# MCU.net
KiCad netlist of a schematic drawn in Altium Designer
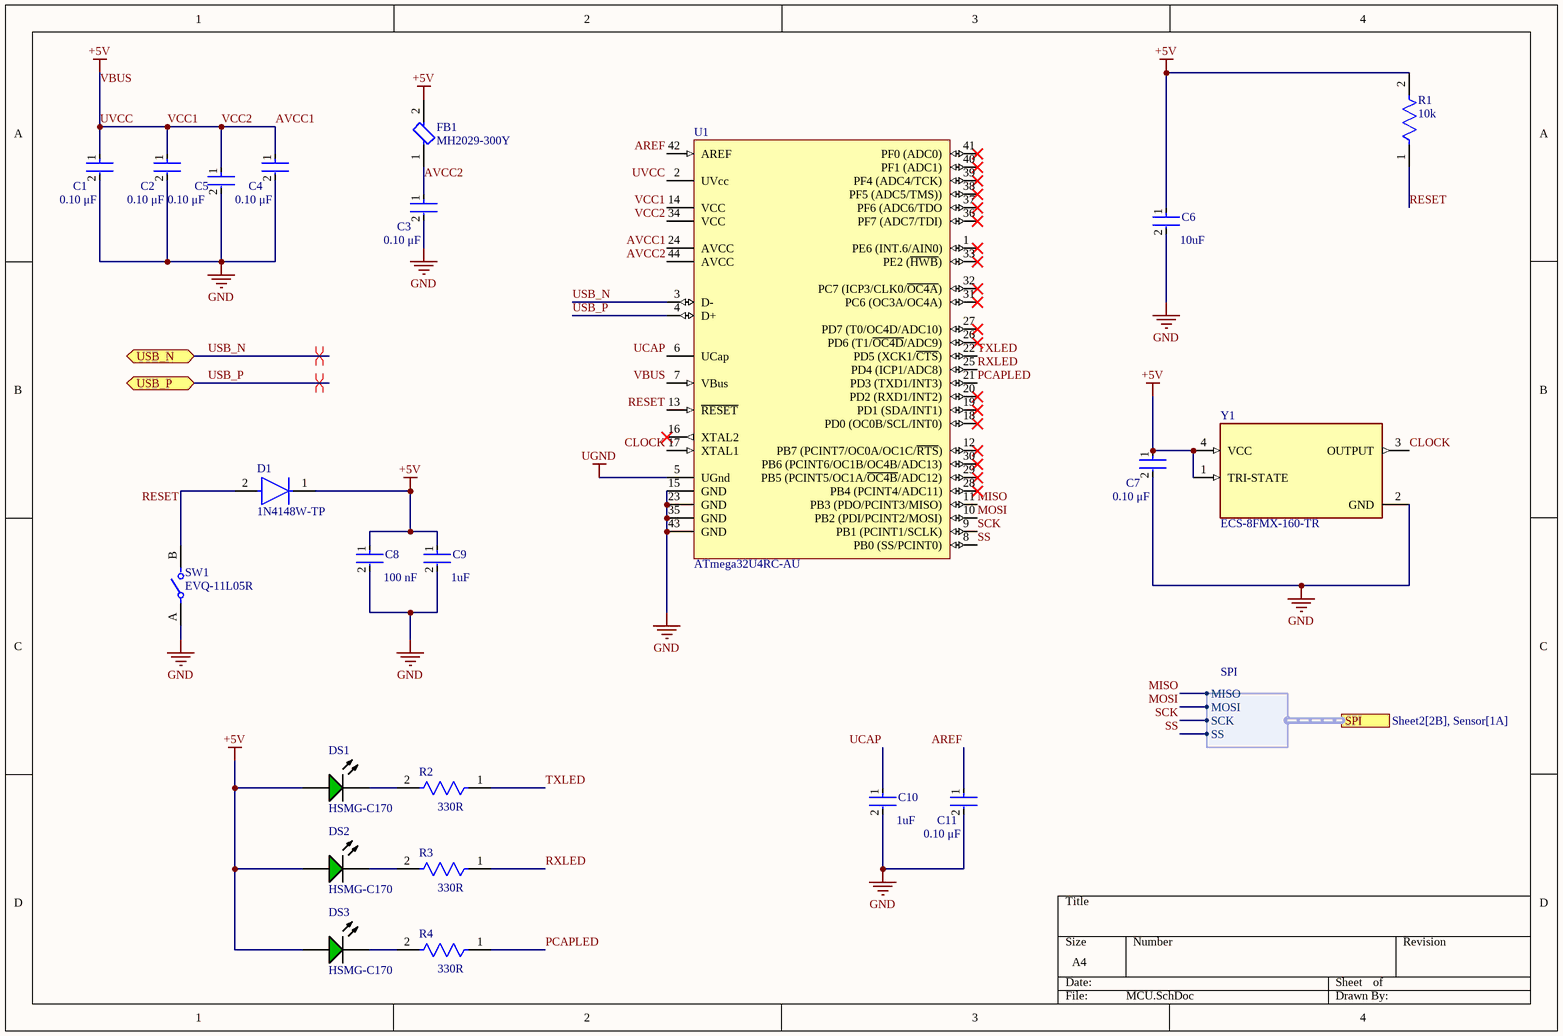
[diagram p0: MCU.SchDoc]

(export (version "E")
  (design (tool "Eeschema 10.0.6"))
  (components
    (comp (ref "C1")
      (value "C0805C104J8RACTU")
      (footprint "FP-C0805C-DN-MFG")
      (description "CAP CER 0.1UF 10V 5% X7R 0805")
      (fields
        (field (name "MANUFACTURER") "KEMET")
        (field (name "TOLERANCE") "0.05")
        (field (name "CAPACITANCE") "0.10 μF")
      )
      (libsource (lib "Altium Content Vault") (part "b4654b650e69147ec39a6b967a45e02"))
    )
    (comp (ref "C2")
      (value "C0805C104J8RACTU")
      (footprint "FP-C0805C-DN-MFG")
      (description "CAP CER 0.1UF 10V 5% X7R 0805")
      (fields
        (field (name "MANUFACTURER") "KEMET")
        (field (name "TOLERANCE") "0.05")
        (field (name "CAPACITANCE") "0.10 μF")
      )
      (libsource (lib "Altium Content Vault") (part "b4654b650e69147ec39a6b967a45e02"))
    )
    (comp (ref "C3")
      (value "C0805C104J8RACTU")
      (footprint "FP-C0805C-DN-MFG")
      (description "CAP CER 0.1UF 10V 5% X7R 0805")
      (fields
        (field (name "MANUFACTURER") "KEMET")
        (field (name "TOLERANCE") "0.05")
        (field (name "CAPACITANCE") "0.10 μF")
      )
      (libsource (lib "Altium Content Vault") (part "b4654b650e69147ec39a6b967a45e02"))
    )
    (comp (ref "C4")
      (value "C0805C104J8RACTU")
      (footprint "FP-C0805C-DN-MFG")
      (description "CAP CER 0.1UF 10V 5% X7R 0805")
      (fields
        (field (name "MANUFACTURER") "KEMET")
        (field (name "TOLERANCE") "0.05")
        (field (name "CAPACITANCE") "0.10 μF")
      )
      (libsource (lib "Altium Content Vault") (part "b4654b650e69147ec39a6b967a45e02"))
    )
    (comp (ref "C5")
      (value "C0805C104J8RACTU")
      (footprint "FP-C0805C-DN-MFG")
      (description "CAP CER 0.1UF 10V 5% X7R 0805")
      (fields
        (field (name "MANUFACTURER") "KEMET")
        (field (name "TOLERANCE") "0.05")
        (field (name "CAPACITANCE") "0.10 μF")
      )
      (libsource (lib "Altium Content Vault") (part "b4654b650e69147ec39a6b967a45e02"))
    )
    (comp (ref "C6")
      (value "C0805C106K8PACTU")
      (footprint "FP-C0805C-DG-MFG")
      (description "CAP CER 10UF 10V X5R 0805")
      (fields
        (field (name "TOLERANCE") "10%")
        (field (name "MANUFACTURER") "Kemet")
        (field (name "CAPACITANCE") "10uF")
      )
      (libsource (lib "Altium Content Vault") (part "11868f565c42a9108669ba33697ecf6"))
    )
    (comp (ref "C7")
      (value "C0805C104J8RACTU")
      (footprint "FP-C0805C-DN-MFG")
      (description "CAP CER 0.1UF 10V 5% X7R 0805")
      (fields
        (field (name "MANUFACTURER") "KEMET")
        (field (name "TOLERANCE") "0.05")
        (field (name "CAPACITANCE") "0.10 μF")
      )
      (libsource (lib "Altium Content Vault") (part "b4654b650e69147ec39a6b967a45e02"))
    )
    (comp (ref "C8")
      (value "CC0805KRX7R7BB104")
      (footprint "FP-CC0805-0_85-MFG")
      (description "CAP CER 0.1UF 16V X7R 0805")
      (fields
        (field (name "MANUFACTURER") "Yageo")
        (field (name "OCTOPART") "https://octopart.com/cc0805krx7r7bb104-yageo-39467769")
        (field (name "CAPACITANCE") "100 nF")
      )
      (libsource (lib "Altium Content Vault") (part "11868f565c42a9108669ba33697ecf6"))
    )
    (comp (ref "C9")
      (value "C0805C106K8PACTU")
      (footprint "FP-C0805C-DG-MFG")
      (description "CAP CER 10UF 10V X5R 0805")
      (fields
        (field (name "TOLERANCE") "10%")
        (field (name "MANUFACTURER") "Kemet")
        (field (name "CAPACITANCE") "1uF")
      )
      (libsource (lib "Altium Content Vault") (part "11868f565c42a9108669ba33697ecf6"))
    )
    (comp (ref "C10")
      (value "C0805C106K8PACTU")
      (footprint "FP-C0805C-DG-MFG")
      (description "CAP CER 10UF 10V X5R 0805")
      (fields
        (field (name "TOLERANCE") "10%")
        (field (name "MANUFACTURER") "Kemet")
        (field (name "CAPACITANCE") "1uF")
      )
      (libsource (lib "Altium Content Vault") (part "11868f565c42a9108669ba33697ecf6"))
    )
    (comp (ref "C11")
      (value "C0805C104J8RACTU")
      (footprint "FP-C0805C-DN-MFG")
      (description "CAP CER 0.1UF 10V 5% X7R 0805")
      (fields
        (field (name "MANUFACTURER") "KEMET")
        (field (name "TOLERANCE") "0.05")
        (field (name "CAPACITANCE") "0.10 μF")
      )
      (libsource (lib "Altium Content Vault") (part "b4654b650e69147ec39a6b967a45e02"))
    )
    (comp (ref "D1")
      (value "1N4148W-TP")
      (footprint "FP-SOD-123-IPC_A")
      (description "DIODE GEN PURP 100V 150MA SOD123")
      (libsource (lib "Altium Content Vault") (part "d7152d700b627762746794eb795d46e"))
    )
    (comp (ref "DS1")
      (value "HSMG-C170")
      (footprint "AVAG-HSMX-C170_V")
      (description "Chip LED, Green, 2.2 V, -40 to 85 degC, 2-Pin SMD, Pb-Free, Tape and Reel")
      (fields (field (name "MANUFACTURER") "Avago"))
      (libsource (lib "Altium Content Vault") (part "LED_GREEN_A1K2-2"))
    )
    (comp (ref "DS2")
      (value "HSMG-C170")
      (footprint "AVAG-HSMX-C170_V")
      (description "Chip LED, Green, 2.2 V, -40 to 85 degC, 2-Pin SMD, Pb-Free, Tape and Reel")
      (fields (field (name "MANUFACTURER") "Avago"))
      (libsource (lib "Altium Content Vault") (part "LED_GREEN_A1K2-2"))
    )
    (comp (ref "DS3")
      (value "HSMG-C170")
      (footprint "AVAG-HSMX-C170_V")
      (description "Chip LED, Green, 2.2 V, -40 to 85 degC, 2-Pin SMD, Pb-Free, Tape and Reel")
      (fields (field (name "MANUFACTURER") "Avago"))
      (libsource (lib "Altium Content Vault") (part "LED_GREEN_A1K2-2"))
    )
    (comp (ref "FB1")
      (value "MH2029-300Y")
      (footprint "FP-MH2029-MFG")
      (description "MH Series High Current Chip Ferrite Beads")
      (fields (field (name "OCTOPART") "https://octopart.com/mh2029-300y-bourns-756929"))
      (libsource (lib "Altium Content Vault") (part "5f30dd21d616792df468990f7003faa"))
    )
    (comp (ref "R1")
      (value "CRCW080522R0FKEA")
      (footprint "FP-CRCW0805-e3-IPC_C")
      (description "RES Thick Film, 22Ω, 1%, 0.125W, 100ppm/°C, 0805")
      (fields (field (name "RESISTANCE") "10k") (field (name "TOLERANCE") "1%"))
      (libsource (lib "Altium Content Vault") (part "1029c3af85768c4190bb7ad29bc67b5"))
    )
    (comp (ref "R2")
      (value "330 R")
      (footprint "FP-CR0805-IPC_B")
      (description "Thick Film Chip Resistors 0805 330Ω 0.125W 1% 100ppm/°C")
      (fields (field (name "TOLERANCE") "1%") (field (name "RESISTANCE") "330R"))
      (libsource (lib "Altium Content Vault") (part "1029c3af85768c4190bb7ad29bc67b5"))
    )
    (comp (ref "R3")
      (value "330 R")
      (footprint "FP-CR0805-IPC_B")
      (description "Thick Film Chip Resistors 0805 330Ω 0.125W 1% 100ppm/°C")
      (fields (field (name "TOLERANCE") "1%") (field (name "RESISTANCE") "330R"))
      (libsource (lib "Altium Content Vault") (part "1029c3af85768c4190bb7ad29bc67b5"))
    )
    (comp (ref "R4")
      (value "330 R")
      (footprint "FP-CR0805-IPC_B")
      (description "Thick Film Chip Resistors 0805 330Ω 0.125W 1% 100ppm/°C")
      (fields (field (name "TOLERANCE") "1%") (field (name "RESISTANCE") "330R"))
      (libsource (lib "Altium Content Vault") (part "1029c3af85768c4190bb7ad29bc67b5"))
    )
    (comp (ref "SW1")
      (value "EVQ-11L05R")
      (footprint "FP-EVQ-11L05R-MFG")
      (description "EVQ-11L05R Switch Tactile N.O. SPST Round Button PC Pins 0.02A 15VDC 1.6N Thru-Hole Radial T/R")
      (libsource (lib "Altium Content Vault") (part "2b0b2b19372efd94fa7681498149756"))
    )
    (comp (ref "U1")
      (value "ATmega32U4RC-AU")
      (footprint "44ML_N")
      (libsource (lib "Altium Content Vault") (part "MC-8B-ATM16U4-SQ44"))
    )
    (comp (ref "Y1")
      (value "ECS-8FMX-160-TR")
      (footprint "OSC_ECS-8FMX-160-TR")
      (description "CMOS Oscillator Enable/Disable 4-SOJ, 5.08mm pitch")
      (libsource (lib "University of Moratuwa") (part "ECS-8FMX-160-TR"))
    )
  )
  (nets
    (net (code "2") (name "+5V") (class "Default")
      (node (ref "C1") (pin "1") (pinfunction "1_1") (pintype "passive"))
      (node (ref "C2") (pin "1") (pinfunction "1_1") (pintype "passive"))
      (node (ref "C4") (pin "1") (pinfunction "1_1") (pintype "passive"))
      (node (ref "C5") (pin "1") (pinfunction "1_1") (pintype "passive"))
      (node (ref "C6") (pin "1") (pinfunction "1_1") (pintype "passive"))
      (node (ref "C7") (pin "1") (pinfunction "1_1") (pintype "passive"))
      (node (ref "C8") (pin "1") (pinfunction "1_1") (pintype "passive"))
      (node (ref "C9") (pin "1") (pinfunction "1_1") (pintype "passive"))
      (node (ref "D1") (pin "1") (pinfunction "C_1") (pintype "passive"))
      (node (ref "DS1") (pin "1") (pinfunction "A_1") (pintype "passive"))
      (node (ref "DS2") (pin "1") (pinfunction "A_1") (pintype "passive"))
      (node (ref "DS3") (pin "1") (pinfunction "A_1") (pintype "passive"))
      (node (ref "FB1") (pin "2") (pinfunction "2_2") (pintype "passive"))
      (node (ref "R1") (pin "2") (pinfunction "2_2") (pintype "passive"))
      (node (ref "U1") (pin "14") (pinfunction "VCC_14") (pintype "power_in"))
      (node (ref "U1") (pin "2") (pinfunction "UVcc_2") (pintype "power_in"))
      (node (ref "U1") (pin "24") (pinfunction "AVCC_24") (pintype "power_in"))
      (node (ref "U1") (pin "34") (pinfunction "VCC_34") (pintype "power_in"))
      (node (ref "U1") (pin "7") (pinfunction "VBus_7") (pintype "input"))
      (node (ref "Y1") (pin "1") (pinfunction "TRI-STATE_1") (pintype "input"))
      (node (ref "Y1") (pin "4") (pinfunction "VCC_4") (pintype "input"))
    )
    (net (code "3") (name "/AREF") (class "Default")
      (node (ref "C11") (pin "1") (pinfunction "1_1") (pintype "passive"))
      (node (ref "U1") (pin "42") (pinfunction "AREF_42") (pintype "input"))
    )
    (net (code "4") (name "/AVCC2") (class "Default")
      (node (ref "C3") (pin "1") (pinfunction "1_1") (pintype "passive"))
      (node (ref "FB1") (pin "1") (pinfunction "1_1") (pintype "passive"))
      (node (ref "U1") (pin "44") (pinfunction "AVCC_44") (pintype "power_in"))
    )
    (net (code "5") (name "/CLOCK") (class "Default")
      (node (ref "U1") (pin "17") (pinfunction "XTAL1_17") (pintype "input"))
      (node (ref "Y1") (pin "3") (pinfunction "OUTPUT_3") (pintype "output"))
    )
    (net (code "6") (name "/MISO") (class "Default")
      (node (ref "U1") (pin "11") (pinfunction "PB3_(PDO/PCINT3/MISO)_11") (pintype "bidirectional"))
    )
    (net (code "7") (name "/MOSI") (class "Default")
      (node (ref "U1") (pin "10") (pinfunction "PB2_(PDI/PCINT2/MOSI)_10") (pintype "bidirectional"))
    )
    (net (code "8") (name "/PCAPLED") (class "Default")
      (node (ref "R4") (pin "1") (pinfunction "1_1") (pintype "passive"))
      (node (ref "U1") (pin "21") (pinfunction "PD3_(TXD1/INT3)_21") (pintype "bidirectional"))
    )
    (net (code "9") (name "/RESET") (class "Default")
      (node (ref "D1") (pin "2") (pinfunction "A_2") (pintype "passive"))
      (node (ref "R1") (pin "1") (pinfunction "1_1") (pintype "passive"))
      (node (ref "SW1") (pin "B") (pinfunction "B_B") (pintype "passive"))
      (node (ref "U1") (pin "13") (pinfunction "~{RESET}_13") (pintype "input"))
    )
    (net (code "10") (name "/RXLED") (class "Default")
      (node (ref "R3") (pin "1") (pinfunction "1_1") (pintype "passive"))
      (node (ref "U1") (pin "25") (pinfunction "PD4_(ICP1/ADC8)_25") (pintype "bidirectional"))
    )
    (net (code "11") (name "/SCK") (class "Default")
      (node (ref "U1") (pin "9") (pinfunction "PB1_(PCINT1/SCLK)_9") (pintype "bidirectional"))
    )
    (net (code "12") (name "/SS") (class "Default")
      (node (ref "U1") (pin "8") (pinfunction "PB0_(SS/PCINT0)_8") (pintype "bidirectional"))
    )
    (net (code "13") (name "/TXLED") (class "Default")
      (node (ref "R2") (pin "1") (pinfunction "1_1") (pintype "passive"))
      (node (ref "U1") (pin "22") (pinfunction "PD5_(XCK1/~{CTS})_22") (pintype "bidirectional"))
    )
    (net (code "14") (name "/UCAP") (class "Default")
      (node (ref "C10") (pin "1") (pinfunction "1_1") (pintype "passive"))
      (node (ref "U1") (pin "6") (pinfunction "UCap_6") (pintype "passive"))
    )
    (net (code "15") (name "/USB_N") (class "Default")
      (node (ref "U1") (pin "3") (pinfunction "D-_3") (pintype "bidirectional"))
    )
    (net (code "16") (name "/USB_P") (class "Default")
      (node (ref "U1") (pin "4") (pinfunction "D+_4") (pintype "bidirectional"))
    )
    (net (code "18") (name "GND") (class "Default")
      (node (ref "C1") (pin "2") (pinfunction "2_2") (pintype "passive"))
      (node (ref "C10") (pin "2") (pinfunction "2_2") (pintype "passive"))
      (node (ref "C11") (pin "2") (pinfunction "2_2") (pintype "passive"))
      (node (ref "C2") (pin "2") (pinfunction "2_2") (pintype "passive"))
      (node (ref "C3") (pin "2") (pinfunction "2_2") (pintype "passive"))
      (node (ref "C4") (pin "2") (pinfunction "2_2") (pintype "passive"))
      (node (ref "C5") (pin "2") (pinfunction "2_2") (pintype "passive"))
      (node (ref "C6") (pin "2") (pinfunction "2_2") (pintype "passive"))
      (node (ref "C7") (pin "2") (pinfunction "2_2") (pintype "passive"))
      (node (ref "C8") (pin "2") (pinfunction "2_2") (pintype "passive"))
      (node (ref "C9") (pin "2") (pinfunction "2_2") (pintype "passive"))
      (node (ref "SW1") (pin "A") (pinfunction "A_A") (pintype "passive"))
      (node (ref "U1") (pin "15") (pinfunction "GND_15") (pintype "power_in"))
      (node (ref "U1") (pin "23") (pinfunction "GND_23") (pintype "power_in"))
      (node (ref "U1") (pin "35") (pinfunction "GND_35") (pintype "power_in"))
      (node (ref "U1") (pin "43") (pinfunction "GND_43") (pintype "power_in"))
      (node (ref "Y1") (pin "2") (pinfunction "GND_2") (pintype "power_in"))
    )
    (net (code "19") (name "Net-(DS1-K)") (class "Default")
      (node (ref "DS1") (pin "2") (pinfunction "K_2") (pintype "passive"))
      (node (ref "R2") (pin "2") (pinfunction "2_2") (pintype "passive"))
    )
    (net (code "20") (name "Net-(DS2-K)") (class "Default")
      (node (ref "DS2") (pin "2") (pinfunction "K_2") (pintype "passive"))
      (node (ref "R3") (pin "2") (pinfunction "2_2") (pintype "passive"))
    )
    (net (code "21") (name "Net-(DS3-K)") (class "Default")
      (node (ref "DS3") (pin "2") (pinfunction "K_2") (pintype "passive"))
      (node (ref "R4") (pin "2") (pinfunction "2_2") (pintype "passive"))
    )
    (net (code "22") (name "UGND") (class "Default")
      (node (ref "U1") (pin "5") (pinfunction "UGnd_5") (pintype "power_in"))
    )
    (net (code "23") (name "unconnected-(U1-PB4_(PCINT4{slash}ADC11)-Pad28)") (class "Default")
      (node (ref "U1") (pin "28") (pinfunction "PB4_(PCINT4/ADC11)_28") (pintype "bidirectional+no_connect"))
    )
    (net (code "24") (name "unconnected-(U1-PB5_(PCINT5{slash}OC1A{slash}~{OC4B}{slash}ADC12)-Pad29)") (class "Default")
      (node (ref "U1") (pin "29") (pinfunction "PB5_(PCINT5/OC1A/~{OC4B}/ADC12)_29") (pintype "bidirectional+no_connect"))
    )
    (net (code "25") (name "unconnected-(U1-PB6_(PCINT6{slash}OC1B{slash}OC4B{slash}ADC13)-Pad30)") (class "Default")
      (node (ref "U1") (pin "30") (pinfunction "PB6_(PCINT6/OC1B/OC4B/ADC13)_30") (pintype "bidirectional+no_connect"))
    )
    (net (code "26") (name "unconnected-(U1-PB7_(PCINT7{slash}OC0A{slash}OC1C{slash}~{RTS})-Pad12)") (class "Default")
      (node (ref "U1") (pin "12") (pinfunction "PB7_(PCINT7/OC0A/OC1C/~{RTS})_12") (pintype "bidirectional+no_connect"))
    )
    (net (code "27") (name "unconnected-(U1-PC6_(OC3A{slash}OC4A)-Pad31)") (class "Default")
      (node (ref "U1") (pin "31") (pinfunction "PC6_(OC3A/OC4A)_31") (pintype "bidirectional+no_connect"))
    )
    (net (code "28") (name "unconnected-(U1-PC7_(ICP3{slash}CLK0{slash}~{OC4A})-Pad32)") (class "Default")
      (node (ref "U1") (pin "32") (pinfunction "PC7_(ICP3/CLK0/~{OC4A})_32") (pintype "bidirectional+no_connect"))
    )
    (net (code "29") (name "unconnected-(U1-PD0_(OC0B{slash}SCL{slash}INT0)-Pad18)") (class "Default")
      (node (ref "U1") (pin "18") (pinfunction "PD0_(OC0B/SCL/INT0)_18") (pintype "bidirectional+no_connect"))
    )
    (net (code "30") (name "unconnected-(U1-PD1_(SDA{slash}INT1)-Pad19)") (class "Default")
      (node (ref "U1") (pin "19") (pinfunction "PD1_(SDA/INT1)_19") (pintype "bidirectional+no_connect"))
    )
    (net (code "31") (name "unconnected-(U1-PD2_(RXD1{slash}INT2)-Pad20)") (class "Default")
      (node (ref "U1") (pin "20") (pinfunction "PD2_(RXD1/INT2)_20") (pintype "bidirectional+no_connect"))
    )
    (net (code "32") (name "unconnected-(U1-PD6_(T1{slash}~{OC4D}{slash}ADC9)-Pad26)") (class "Default")
      (node (ref "U1") (pin "26") (pinfunction "PD6_(T1/~{OC4D}/ADC9)_26") (pintype "bidirectional+no_connect"))
    )
    (net (code "33") (name "unconnected-(U1-PD7_(T0{slash}OC4D{slash}ADC10)-Pad27)") (class "Default")
      (node (ref "U1") (pin "27") (pinfunction "PD7_(T0/OC4D/ADC10)_27") (pintype "bidirectional+no_connect"))
    )
    (net (code "34") (name "unconnected-(U1-PE2_(~{HWB})-Pad33)") (class "Default")
      (node (ref "U1") (pin "33") (pinfunction "PE2_(~{HWB})_33") (pintype "bidirectional+no_connect"))
    )
    (net (code "35") (name "unconnected-(U1-PE6_(INT.6{slash}AIN0)-Pad1)") (class "Default")
      (node (ref "U1") (pin "1") (pinfunction "PE6_(INT.6/AIN0)_1") (pintype "bidirectional+no_connect"))
    )
    (net (code "36") (name "unconnected-(U1-PF0_(ADC0)-Pad41)") (class "Default")
      (node (ref "U1") (pin "41") (pinfunction "PF0_(ADC0)_41") (pintype "bidirectional+no_connect"))
    )
    (net (code "37") (name "unconnected-(U1-PF1_(ADC1)-Pad40)") (class "Default")
      (node (ref "U1") (pin "40") (pinfunction "PF1_(ADC1)_40") (pintype "bidirectional+no_connect"))
    )
    (net (code "38") (name "unconnected-(U1-PF4_(ADC4{slash}TCK)-Pad39)") (class "Default")
      (node (ref "U1") (pin "39") (pinfunction "PF4_(ADC4/TCK)_39") (pintype "bidirectional+no_connect"))
    )
    (net (code "39") (name "unconnected-(U1-PF5_(ADC5{slash}TMS))-Pad38)") (class "Default")
      (node (ref "U1") (pin "38") (pinfunction "PF5_(ADC5/TMS))_38") (pintype "bidirectional+no_connect"))
    )
    (net (code "40") (name "unconnected-(U1-PF6_(ADC6{slash}TDO-Pad37)") (class "Default")
      (node (ref "U1") (pin "37") (pinfunction "PF6_(ADC6/TDO_37") (pintype "bidirectional+no_connect"))
    )
    (net (code "41") (name "unconnected-(U1-PF7_(ADC7{slash}TDI)-Pad36)") (class "Default")
      (node (ref "U1") (pin "36") (pinfunction "PF7_(ADC7/TDI)_36") (pintype "bidirectional+no_connect"))
    )
    (net (code "42") (name "unconnected-(U1-XTAL2-Pad16)") (class "Default")
      (node (ref "U1") (pin "16") (pinfunction "XTAL2_16") (pintype "output+no_connect"))
    )
  )
)
